# CNC-KeyboardBoard.net
KiCad netlist of a schematic drawn in EAGLE
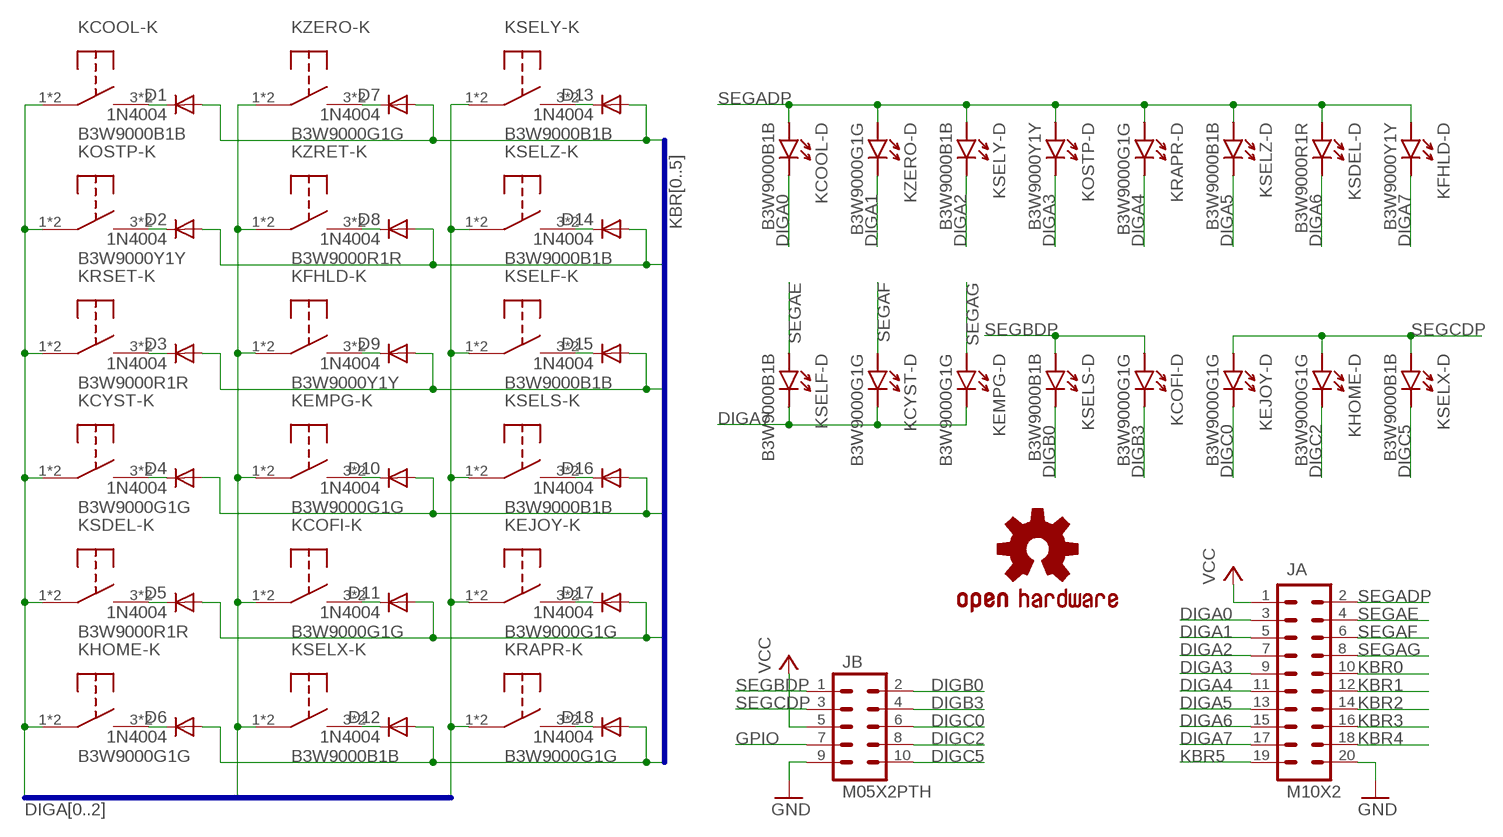
[diagram p0: schematic, sheet 1]

(export (version "E")
  (design (tool "Eeschema 10.0.6"))
  (components
    (comp (ref "D1")
      (value "1N4004")
      (footprint "eagle-import:DO41-10")
      (libsource (lib "eagle-import") (part "1N4004"))
    )
    (comp (ref "D2")
      (value "1N4004")
      (footprint "eagle-import:DO41-10")
      (libsource (lib "eagle-import") (part "1N4004"))
    )
    (comp (ref "D3")
      (value "1N4004")
      (footprint "eagle-import:DO41-10")
      (libsource (lib "eagle-import") (part "1N4004"))
    )
    (comp (ref "D4")
      (value "1N4004")
      (footprint "eagle-import:DO41-10")
      (libsource (lib "eagle-import") (part "1N4004"))
    )
    (comp (ref "D5")
      (value "1N4004")
      (footprint "eagle-import:DO41-10")
      (libsource (lib "eagle-import") (part "1N4004"))
    )
    (comp (ref "D6")
      (value "1N4004")
      (footprint "eagle-import:DO41-10")
      (libsource (lib "eagle-import") (part "1N4004"))
    )
    (comp (ref "D7")
      (value "1N4004")
      (footprint "eagle-import:DO41-10")
      (libsource (lib "eagle-import") (part "1N4004"))
    )
    (comp (ref "D8")
      (value "1N4004")
      (footprint "eagle-import:DO41-10")
      (libsource (lib "eagle-import") (part "1N4004"))
    )
    (comp (ref "D9")
      (value "1N4004")
      (footprint "eagle-import:DO41-10")
      (libsource (lib "eagle-import") (part "1N4004"))
    )
    (comp (ref "D10")
      (value "1N4004")
      (footprint "eagle-import:DO41-10")
      (libsource (lib "eagle-import") (part "1N4004"))
    )
    (comp (ref "D11")
      (value "1N4004")
      (footprint "eagle-import:DO41-10")
      (libsource (lib "eagle-import") (part "1N4004"))
    )
    (comp (ref "D12")
      (value "1N4004")
      (footprint "eagle-import:DO41-10")
      (libsource (lib "eagle-import") (part "1N4004"))
    )
    (comp (ref "D13")
      (value "1N4004")
      (footprint "eagle-import:DO41-10")
      (libsource (lib "eagle-import") (part "1N4004"))
    )
    (comp (ref "D14")
      (value "1N4004")
      (footprint "eagle-import:DO41-10")
      (libsource (lib "eagle-import") (part "1N4004"))
    )
    (comp (ref "D15")
      (value "1N4004")
      (footprint "eagle-import:DO41-10")
      (libsource (lib "eagle-import") (part "1N4004"))
    )
    (comp (ref "D16")
      (value "1N4004")
      (footprint "eagle-import:DO41-10")
      (libsource (lib "eagle-import") (part "1N4004"))
    )
    (comp (ref "D17")
      (value "1N4004")
      (footprint "eagle-import:DO41-10")
      (libsource (lib "eagle-import") (part "1N4004"))
    )
    (comp (ref "D18")
      (value "1N4004")
      (footprint "eagle-import:DO41-10")
      (libsource (lib "eagle-import") (part "1N4004"))
    )
    (comp (ref "JA")
      (value "M10X2")
      (footprint "eagle-import:2X10")
      (libsource (lib "eagle-import") (part "M10X2"))
    )
    (comp (ref "JB")
      (value "M05X2PTH")
      (footprint "eagle-import:AVR_ICSP")
      (libsource (lib "eagle-import") (part "M05X2PTH"))
    )
    (comp (ref "KCOFI")
      (value "B3W9000G1G")
      (footprint "eagle-import:OMRON_B3W90")
      (libsource (lib "eagle-import") (part "B3W9000G1G"))
    )
    (comp (ref "KCOOL")
      (value "B3W9000B1B")
      (footprint "eagle-import:OMRON_B3W90")
      (libsource (lib "eagle-import") (part "B3W9000B1B"))
    )
    (comp (ref "KCYST")
      (value "B3W9000G1G")
      (footprint "eagle-import:OMRON_B3W90")
      (libsource (lib "eagle-import") (part "B3W9000G1G"))
    )
    (comp (ref "KEJOY")
      (value "B3W9000G1G")
      (footprint "eagle-import:OMRON_B3W90")
      (libsource (lib "eagle-import") (part "B3W9000G1G"))
    )
    (comp (ref "KEMPG")
      (value "B3W9000G1G")
      (footprint "eagle-import:OMRON_B3W90")
      (libsource (lib "eagle-import") (part "B3W9000G1G"))
    )
    (comp (ref "KFHLD")
      (value "B3W9000Y1Y")
      (footprint "eagle-import:OMRON_B3W90")
      (libsource (lib "eagle-import") (part "B3W9000Y1Y"))
    )
    (comp (ref "KHOME")
      (value "B3W9000G1G")
      (footprint "eagle-import:OMRON_B3W90")
      (libsource (lib "eagle-import") (part "B3W9000G1G"))
    )
    (comp (ref "KOSTP")
      (value "B3W9000Y1Y")
      (footprint "eagle-import:OMRON_B3W90")
      (libsource (lib "eagle-import") (part "B3W9000Y1Y"))
    )
    (comp (ref "KRAPR")
      (value "B3W9000G1G")
      (footprint "eagle-import:OMRON_B3W90")
      (libsource (lib "eagle-import") (part "B3W9000G1G"))
    )
    (comp (ref "KRSET")
      (value "B3W9000R1R")
      (footprint "eagle-import:OMRON_B3W90")
      (libsource (lib "eagle-import") (part "B3W9000R1R"))
    )
    (comp (ref "KSDEL")
      (value "B3W9000R1R")
      (footprint "eagle-import:OMRON_B3W90")
      (libsource (lib "eagle-import") (part "B3W9000R1R"))
    )
    (comp (ref "KSELF")
      (value "B3W9000B1B")
      (footprint "eagle-import:OMRON_B3W90")
      (libsource (lib "eagle-import") (part "B3W9000B1B"))
    )
    (comp (ref "KSELS")
      (value "B3W9000B1B")
      (footprint "eagle-import:OMRON_B3W90")
      (libsource (lib "eagle-import") (part "B3W9000B1B"))
    )
    (comp (ref "KSELX")
      (value "B3W9000B1B")
      (footprint "eagle-import:OMRON_B3W90")
      (libsource (lib "eagle-import") (part "B3W9000B1B"))
    )
    (comp (ref "KSELY")
      (value "B3W9000B1B")
      (footprint "eagle-import:OMRON_B3W90")
      (libsource (lib "eagle-import") (part "B3W9000B1B"))
    )
    (comp (ref "KSELZ")
      (value "B3W9000B1B")
      (footprint "eagle-import:OMRON_B3W90")
      (libsource (lib "eagle-import") (part "B3W9000B1B"))
    )
    (comp (ref "KZERO")
      (value "B3W9000G1G")
      (footprint "eagle-import:OMRON_B3W90")
      (libsource (lib "eagle-import") (part "B3W9000G1G"))
    )
    (comp (ref "KZRET")
      (value "B3W9000R1R")
      (footprint "eagle-import:OMRON_B3W90")
      (libsource (lib "eagle-import") (part "B3W9000R1R"))
    )
    (comp (ref "U$1")
      (value "SPARKFUN_OSHW-LOGOL")
      (footprint "eagle-import:SPARKFUN_OSHW-LOGO-L")
      (libsource (lib "eagle-import") (part "SPARKFUN_OSHW-LOGOL"))
    )
  )
  (nets
    (net (code "1") (name "/DIGA0") (class "Default")
      (node (ref "JA") (pin "3") (pinfunction "3_3") (pintype "passive"))
      (node (ref "KCOOL") (pin "1") (pinfunction "P$1_1") (pintype "passive"))
      (node (ref "KCOOL") (pin "2") (pinfunction "P$1_2") (pintype "passive"))
      (node (ref "KCOOL") (pin "6") (pinfunction "K_6") (pintype "output"))
      (node (ref "KCYST") (pin "1") (pinfunction "P$1_1") (pintype "passive"))
      (node (ref "KCYST") (pin "2") (pinfunction "P$1_2") (pintype "passive"))
      (node (ref "KHOME") (pin "1") (pinfunction "P$1_1") (pintype "passive"))
      (node (ref "KHOME") (pin "2") (pinfunction "P$1_2") (pintype "passive"))
      (node (ref "KOSTP") (pin "1") (pinfunction "P$1_1") (pintype "passive"))
      (node (ref "KOSTP") (pin "2") (pinfunction "P$1_2") (pintype "passive"))
      (node (ref "KRSET") (pin "1") (pinfunction "P$1_1") (pintype "passive"))
      (node (ref "KRSET") (pin "2") (pinfunction "P$1_2") (pintype "passive"))
      (node (ref "KSDEL") (pin "1") (pinfunction "P$1_1") (pintype "passive"))
      (node (ref "KSDEL") (pin "2") (pinfunction "P$1_2") (pintype "passive"))
    )
    (net (code "2") (name "/DIGA1") (class "Default")
      (node (ref "JA") (pin "5") (pinfunction "5_5") (pintype "passive"))
      (node (ref "KCOFI") (pin "1") (pinfunction "P$1_1") (pintype "passive"))
      (node (ref "KCOFI") (pin "2") (pinfunction "P$1_2") (pintype "passive"))
      (node (ref "KEMPG") (pin "1") (pinfunction "P$1_1") (pintype "passive"))
      (node (ref "KEMPG") (pin "2") (pinfunction "P$1_2") (pintype "passive"))
      (node (ref "KFHLD") (pin "1") (pinfunction "P$1_1") (pintype "passive"))
      (node (ref "KFHLD") (pin "2") (pinfunction "P$1_2") (pintype "passive"))
      (node (ref "KSELX") (pin "1") (pinfunction "P$1_1") (pintype "passive"))
      (node (ref "KSELX") (pin "2") (pinfunction "P$1_2") (pintype "passive"))
      (node (ref "KZERO") (pin "1") (pinfunction "P$1_1") (pintype "passive"))
      (node (ref "KZERO") (pin "2") (pinfunction "P$1_2") (pintype "passive"))
      (node (ref "KZERO") (pin "6") (pinfunction "K_6") (pintype "output"))
      (node (ref "KZRET") (pin "1") (pinfunction "P$1_1") (pintype "passive"))
      (node (ref "KZRET") (pin "2") (pinfunction "P$1_2") (pintype "passive"))
    )
    (net (code "3") (name "/DIGA2") (class "Default")
      (node (ref "JA") (pin "7") (pinfunction "7_7") (pintype "passive"))
      (node (ref "KEJOY") (pin "1") (pinfunction "P$1_1") (pintype "passive"))
      (node (ref "KEJOY") (pin "2") (pinfunction "P$1_2") (pintype "passive"))
      (node (ref "KRAPR") (pin "1") (pinfunction "P$1_1") (pintype "passive"))
      (node (ref "KRAPR") (pin "2") (pinfunction "P$1_2") (pintype "passive"))
      (node (ref "KSELF") (pin "1") (pinfunction "P$1_1") (pintype "passive"))
      (node (ref "KSELF") (pin "2") (pinfunction "P$1_2") (pintype "passive"))
      (node (ref "KSELS") (pin "1") (pinfunction "P$1_1") (pintype "passive"))
      (node (ref "KSELS") (pin "2") (pinfunction "P$1_2") (pintype "passive"))
      (node (ref "KSELY") (pin "1") (pinfunction "P$1_1") (pintype "passive"))
      (node (ref "KSELY") (pin "2") (pinfunction "P$1_2") (pintype "passive"))
      (node (ref "KSELY") (pin "6") (pinfunction "K_6") (pintype "output"))
      (node (ref "KSELZ") (pin "1") (pinfunction "P$1_1") (pintype "passive"))
      (node (ref "KSELZ") (pin "2") (pinfunction "P$1_2") (pintype "passive"))
    )
    (net (code "4") (name "/DIGA3") (class "Default")
      (node (ref "JA") (pin "9") (pinfunction "9_9") (pintype "passive"))
      (node (ref "KOSTP") (pin "6") (pinfunction "K_6") (pintype "output"))
    )
    (net (code "5") (name "/DIGA4") (class "Default")
      (node (ref "JA") (pin "11") (pinfunction "11_11") (pintype "passive"))
      (node (ref "KRAPR") (pin "6") (pinfunction "K_6") (pintype "output"))
    )
    (net (code "6") (name "/DIGA5") (class "Default")
      (node (ref "JA") (pin "13") (pinfunction "13_13") (pintype "passive"))
      (node (ref "KSELZ") (pin "6") (pinfunction "K_6") (pintype "output"))
    )
    (net (code "7") (name "/DIGA6") (class "Default")
      (node (ref "JA") (pin "15") (pinfunction "15_15") (pintype "passive"))
      (node (ref "KSDEL") (pin "6") (pinfunction "K_6") (pintype "output"))
    )
    (net (code "8") (name "/DIGA7") (class "Default")
      (node (ref "JA") (pin "17") (pinfunction "17_17") (pintype "passive"))
      (node (ref "KCYST") (pin "6") (pinfunction "K_6") (pintype "output"))
      (node (ref "KEMPG") (pin "6") (pinfunction "K_6") (pintype "output"))
      (node (ref "KFHLD") (pin "6") (pinfunction "K_6") (pintype "output"))
      (node (ref "KSELF") (pin "6") (pinfunction "K_6") (pintype "output"))
    )
    (net (code "10") (name "/DIGB0") (class "Default")
      (node (ref "JB") (pin "2") (pinfunction "2_2") (pintype "passive"))
      (node (ref "KSELS") (pin "6") (pinfunction "K_6") (pintype "output"))
    )
    (net (code "11") (name "/DIGB3") (class "Default")
      (node (ref "JB") (pin "4") (pinfunction "4_4") (pintype "passive"))
      (node (ref "KCOFI") (pin "6") (pinfunction "K_6") (pintype "output"))
    )
    (net (code "12") (name "/DIGC0") (class "Default")
      (node (ref "JB") (pin "6") (pinfunction "6_6") (pintype "passive"))
      (node (ref "KEJOY") (pin "6") (pinfunction "K_6") (pintype "output"))
    )
    (net (code "13") (name "/DIGC2") (class "Default")
      (node (ref "JB") (pin "8") (pinfunction "8_8") (pintype "passive"))
      (node (ref "KHOME") (pin "6") (pinfunction "K_6") (pintype "output"))
    )
    (net (code "14") (name "/DIGC5") (class "Default")
      (node (ref "JB") (pin "10") (pinfunction "10_10") (pintype "passive"))
      (node (ref "KSELX") (pin "6") (pinfunction "K_6") (pintype "output"))
    )
    (net (code "15") (name "/GPIO") (class "Default")
      (node (ref "JB") (pin "7") (pinfunction "7_7") (pintype "passive"))
    )
    (net (code "16") (name "/KBR0") (class "Default")
      (node (ref "D1") (pin "A") (pinfunction "A_A") (pintype "passive"))
      (node (ref "D13") (pin "A") (pinfunction "A_A") (pintype "passive"))
      (node (ref "D7") (pin "A") (pinfunction "A_A") (pintype "passive"))
      (node (ref "JA") (pin "10") (pinfunction "10_10") (pintype "passive"))
    )
    (net (code "17") (name "/KBR1") (class "Default")
      (node (ref "D14") (pin "A") (pinfunction "A_A") (pintype "passive"))
      (node (ref "D2") (pin "A") (pinfunction "A_A") (pintype "passive"))
      (node (ref "D8") (pin "A") (pinfunction "A_A") (pintype "passive"))
      (node (ref "JA") (pin "12") (pinfunction "12_12") (pintype "passive"))
    )
    (net (code "18") (name "/KBR2") (class "Default")
      (node (ref "D15") (pin "A") (pinfunction "A_A") (pintype "passive"))
      (node (ref "D3") (pin "A") (pinfunction "A_A") (pintype "passive"))
      (node (ref "D9") (pin "A") (pinfunction "A_A") (pintype "passive"))
      (node (ref "JA") (pin "14") (pinfunction "14_14") (pintype "passive"))
    )
    (net (code "19") (name "/KBR3") (class "Default")
      (node (ref "D10") (pin "A") (pinfunction "A_A") (pintype "passive"))
      (node (ref "D16") (pin "A") (pinfunction "A_A") (pintype "passive"))
      (node (ref "D4") (pin "A") (pinfunction "A_A") (pintype "passive"))
      (node (ref "JA") (pin "16") (pinfunction "16_16") (pintype "passive"))
    )
    (net (code "20") (name "/KBR4") (class "Default")
      (node (ref "D11") (pin "A") (pinfunction "A_A") (pintype "passive"))
      (node (ref "D17") (pin "A") (pinfunction "A_A") (pintype "passive"))
      (node (ref "D5") (pin "A") (pinfunction "A_A") (pintype "passive"))
      (node (ref "JA") (pin "18") (pinfunction "18_18") (pintype "passive"))
    )
    (net (code "21") (name "/KBR5") (class "Default")
      (node (ref "D12") (pin "A") (pinfunction "A_A") (pintype "passive"))
      (node (ref "D18") (pin "A") (pinfunction "A_A") (pintype "passive"))
      (node (ref "D6") (pin "A") (pinfunction "A_A") (pintype "passive"))
      (node (ref "JA") (pin "19") (pinfunction "19_19") (pintype "passive"))
    )
    (net (code "23") (name "/SEGADP") (class "Default")
      (node (ref "JA") (pin "2") (pinfunction "2_2") (pintype "passive"))
      (node (ref "KCOOL") (pin "5") (pinfunction "A_5") (pintype "input"))
      (node (ref "KFHLD") (pin "5") (pinfunction "A_5") (pintype "input"))
      (node (ref "KOSTP") (pin "5") (pinfunction "A_5") (pintype "input"))
      (node (ref "KRAPR") (pin "5") (pinfunction "A_5") (pintype "input"))
      (node (ref "KSDEL") (pin "5") (pinfunction "A_5") (pintype "input"))
      (node (ref "KSELY") (pin "5") (pinfunction "A_5") (pintype "input"))
      (node (ref "KSELZ") (pin "5") (pinfunction "A_5") (pintype "input"))
      (node (ref "KZERO") (pin "5") (pinfunction "A_5") (pintype "input"))
    )
    (net (code "24") (name "/SEGAE") (class "Default")
      (node (ref "JA") (pin "4") (pinfunction "4_4") (pintype "passive"))
      (node (ref "KSELF") (pin "5") (pinfunction "A_5") (pintype "input"))
    )
    (net (code "25") (name "/SEGAF") (class "Default")
      (node (ref "JA") (pin "6") (pinfunction "6_6") (pintype "passive"))
      (node (ref "KCYST") (pin "5") (pinfunction "A_5") (pintype "input"))
    )
    (net (code "26") (name "/SEGAG") (class "Default")
      (node (ref "JA") (pin "8") (pinfunction "8_8") (pintype "passive"))
      (node (ref "KEMPG") (pin "5") (pinfunction "A_5") (pintype "input"))
    )
    (net (code "27") (name "/SEGBDP") (class "Default")
      (node (ref "JB") (pin "1") (pinfunction "1_1") (pintype "passive"))
      (node (ref "KCOFI") (pin "5") (pinfunction "A_5") (pintype "input"))
      (node (ref "KSELS") (pin "5") (pinfunction "A_5") (pintype "input"))
    )
    (net (code "28") (name "/SEGCDP") (class "Default")
      (node (ref "JB") (pin "3") (pinfunction "3_3") (pintype "passive"))
      (node (ref "KEJOY") (pin "5") (pinfunction "A_5") (pintype "input"))
      (node (ref "KHOME") (pin "5") (pinfunction "A_5") (pintype "input"))
      (node (ref "KSELX") (pin "5") (pinfunction "A_5") (pintype "input"))
    )
    (net (code "29") (name "GND") (class "Default")
      (node (ref "JA") (pin "20") (pinfunction "20_20") (pintype "passive"))
      (node (ref "JB") (pin "9") (pinfunction "9_9") (pintype "passive"))
    )
    (net (code "30") (name "Net-(D1-PadC)") (class "Default")
      (node (ref "D1") (pin "C") (pinfunction "C_C") (pintype "passive"))
      (node (ref "KCOOL") (pin "3") (pinfunction "P$2_3") (pintype "passive"))
      (node (ref "KCOOL") (pin "4") (pinfunction "P$2_4") (pintype "passive"))
    )
    (net (code "31") (name "Net-(D2-PadC)") (class "Default")
      (node (ref "D2") (pin "C") (pinfunction "C_C") (pintype "passive"))
      (node (ref "KOSTP") (pin "3") (pinfunction "P$2_3") (pintype "passive"))
      (node (ref "KOSTP") (pin "4") (pinfunction "P$2_4") (pintype "passive"))
    )
    (net (code "32") (name "Net-(D3-PadC)") (class "Default")
      (node (ref "D3") (pin "C") (pinfunction "C_C") (pintype "passive"))
      (node (ref "KRSET") (pin "3") (pinfunction "P$2_3") (pintype "passive"))
      (node (ref "KRSET") (pin "4") (pinfunction "P$2_4") (pintype "passive"))
    )
    (net (code "33") (name "Net-(D4-PadC)") (class "Default")
      (node (ref "D4") (pin "C") (pinfunction "C_C") (pintype "passive"))
      (node (ref "KCYST") (pin "3") (pinfunction "P$2_3") (pintype "passive"))
      (node (ref "KCYST") (pin "4") (pinfunction "P$2_4") (pintype "passive"))
    )
    (net (code "34") (name "Net-(D5-PadC)") (class "Default")
      (node (ref "D5") (pin "C") (pinfunction "C_C") (pintype "passive"))
      (node (ref "KSDEL") (pin "3") (pinfunction "P$2_3") (pintype "passive"))
      (node (ref "KSDEL") (pin "4") (pinfunction "P$2_4") (pintype "passive"))
    )
    (net (code "35") (name "Net-(D6-PadC)") (class "Default")
      (node (ref "D6") (pin "C") (pinfunction "C_C") (pintype "passive"))
      (node (ref "KHOME") (pin "3") (pinfunction "P$2_3") (pintype "passive"))
      (node (ref "KHOME") (pin "4") (pinfunction "P$2_4") (pintype "passive"))
    )
    (net (code "36") (name "Net-(D7-PadC)") (class "Default")
      (node (ref "D7") (pin "C") (pinfunction "C_C") (pintype "passive"))
      (node (ref "KZERO") (pin "3") (pinfunction "P$2_3") (pintype "passive"))
      (node (ref "KZERO") (pin "4") (pinfunction "P$2_4") (pintype "passive"))
    )
    (net (code "37") (name "Net-(D8-PadC)") (class "Default")
      (node (ref "D8") (pin "C") (pinfunction "C_C") (pintype "passive"))
      (node (ref "KZRET") (pin "3") (pinfunction "P$2_3") (pintype "passive"))
      (node (ref "KZRET") (pin "4") (pinfunction "P$2_4") (pintype "passive"))
    )
    (net (code "38") (name "Net-(D9-PadC)") (class "Default")
      (node (ref "D9") (pin "C") (pinfunction "C_C") (pintype "passive"))
      (node (ref "KFHLD") (pin "3") (pinfunction "P$2_3") (pintype "passive"))
      (node (ref "KFHLD") (pin "4") (pinfunction "P$2_4") (pintype "passive"))
    )
    (net (code "39") (name "Net-(D10-PadC)") (class "Default")
      (node (ref "D10") (pin "C") (pinfunction "C_C") (pintype "passive"))
      (node (ref "KEMPG") (pin "3") (pinfunction "P$2_3") (pintype "passive"))
      (node (ref "KEMPG") (pin "4") (pinfunction "P$2_4") (pintype "passive"))
    )
    (net (code "40") (name "Net-(D11-PadC)") (class "Default")
      (node (ref "D11") (pin "C") (pinfunction "C_C") (pintype "passive"))
      (node (ref "KCOFI") (pin "3") (pinfunction "P$2_3") (pintype "passive"))
      (node (ref "KCOFI") (pin "4") (pinfunction "P$2_4") (pintype "passive"))
    )
    (net (code "41") (name "Net-(D12-PadC)") (class "Default")
      (node (ref "D12") (pin "C") (pinfunction "C_C") (pintype "passive"))
      (node (ref "KSELX") (pin "3") (pinfunction "P$2_3") (pintype "passive"))
      (node (ref "KSELX") (pin "4") (pinfunction "P$2_4") (pintype "passive"))
    )
    (net (code "42") (name "Net-(D13-PadC)") (class "Default")
      (node (ref "D13") (pin "C") (pinfunction "C_C") (pintype "passive"))
      (node (ref "KSELY") (pin "3") (pinfunction "P$2_3") (pintype "passive"))
      (node (ref "KSELY") (pin "4") (pinfunction "P$2_4") (pintype "passive"))
    )
    (net (code "43") (name "Net-(D14-PadC)") (class "Default")
      (node (ref "D14") (pin "C") (pinfunction "C_C") (pintype "passive"))
      (node (ref "KSELZ") (pin "3") (pinfunction "P$2_3") (pintype "passive"))
      (node (ref "KSELZ") (pin "4") (pinfunction "P$2_4") (pintype "passive"))
    )
    (net (code "44") (name "Net-(D15-PadC)") (class "Default")
      (node (ref "D15") (pin "C") (pinfunction "C_C") (pintype "passive"))
      (node (ref "KSELF") (pin "3") (pinfunction "P$2_3") (pintype "passive"))
      (node (ref "KSELF") (pin "4") (pinfunction "P$2_4") (pintype "passive"))
    )
    (net (code "45") (name "Net-(D16-PadC)") (class "Default")
      (node (ref "D16") (pin "C") (pinfunction "C_C") (pintype "passive"))
      (node (ref "KSELS") (pin "3") (pinfunction "P$2_3") (pintype "passive"))
      (node (ref "KSELS") (pin "4") (pinfunction "P$2_4") (pintype "passive"))
    )
    (net (code "46") (name "Net-(D17-PadC)") (class "Default")
      (node (ref "D17") (pin "C") (pinfunction "C_C") (pintype "passive"))
      (node (ref "KEJOY") (pin "3") (pinfunction "P$2_3") (pintype "passive"))
      (node (ref "KEJOY") (pin "4") (pinfunction "P$2_4") (pintype "passive"))
    )
    (net (code "47") (name "Net-(D18-PadC)") (class "Default")
      (node (ref "D18") (pin "C") (pinfunction "C_C") (pintype "passive"))
      (node (ref "KRAPR") (pin "3") (pinfunction "P$2_3") (pintype "passive"))
      (node (ref "KRAPR") (pin "4") (pinfunction "P$2_4") (pintype "passive"))
    )
    (net (code "48") (name "VCC") (class "Default")
      (node (ref "JA") (pin "1") (pinfunction "1_1") (pintype "passive"))
      (node (ref "JB") (pin "5") (pinfunction "5_5") (pintype "passive"))
    )
  )
)
